# RF_PATH.net
KiCad netlist of a schematic drawn in Altium Designer
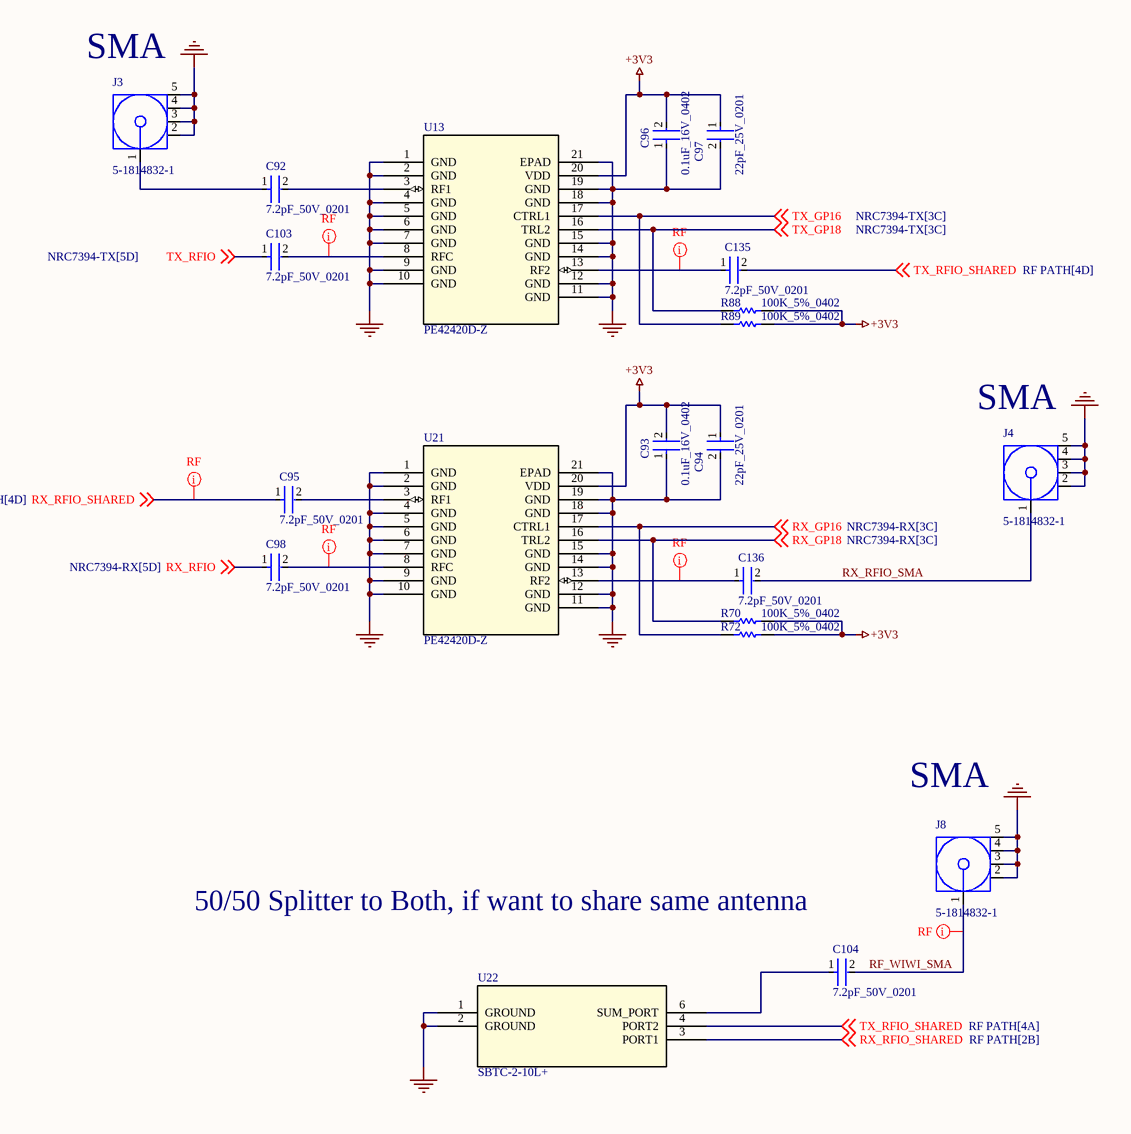
[diagram p0: RF PATH.SchDoc]

(export (version "E")
  (design (tool "Eeschema 10.0.6"))
  (components
    (comp (ref "C92")
      (value "7.2pF_50V_0201")
      (footprint "FP-GRM033-0_03-IPC_B")
      (description "Chip Multilayer Ceramic Capacitors for General Purpose, 0201, 7.2pF, C0G, 30ppm/°C, 0.1pF, 50V")
      (libsource (lib "Altium Content Vault") (part "b4654b650e69147ec39a6b967a45e02"))
    )
    (comp (ref "C93")
      (value "0.1uF_16V_0402")
      (footprint "FP-C0402-BB-MFG")
      (description "CAP CER 0.1UF 16V 20% X7R 0402")
      (fields
        (field (name "MANUFACTURER") "Kemet")
        (field (name "OCTOPART") "https://octopart.com/c0402c104m4ractu-kemet-10476575")
      )
      (libsource (lib "Altium Content Vault") (part "b4654b650e69147ec39a6b967a45e02"))
    )
    (comp (ref "C94")
      (value "22pF_25V_0201")
      (footprint "FP-0201-L_0_6_0_09-W_0_3-MFG")
      (description "General Purpose Ceramic Capacitor, 0201, 22pF, 5%, C0G, 30ppm/°C, 25V")
      (fields (field (name "VOLTAGE") "25V") (field (name "TOLERANCE") "5%"))
      (libsource (lib "Altium Content Vault") (part "b4654b650e69147ec39a6b967a45e02"))
    )
    (comp (ref "C95")
      (value "7.2pF_50V_0201")
      (footprint "FP-GRM033-0_03-IPC_B")
      (description "Chip Multilayer Ceramic Capacitors for General Purpose, 0201, 7.2pF, C0G, 30ppm/°C, 0.1pF, 50V")
      (libsource (lib "Altium Content Vault") (part "b4654b650e69147ec39a6b967a45e02"))
    )
    (comp (ref "C96")
      (value "0.1uF_16V_0402")
      (footprint "FP-C0402-BB-MFG")
      (description "CAP CER 0.1UF 16V 20% X7R 0402")
      (fields
        (field (name "MANUFACTURER") "Kemet")
        (field (name "OCTOPART") "https://octopart.com/c0402c104m4ractu-kemet-10476575")
      )
      (libsource (lib "Altium Content Vault") (part "b4654b650e69147ec39a6b967a45e02"))
    )
    (comp (ref "C97")
      (value "22pF_25V_0201")
      (footprint "FP-0201-L_0_6_0_09-W_0_3-MFG")
      (description "General Purpose Ceramic Capacitor, 0201, 22pF, 5%, C0G, 30ppm/°C, 25V")
      (fields (field (name "VOLTAGE") "25V") (field (name "TOLERANCE") "5%"))
      (libsource (lib "Altium Content Vault") (part "b4654b650e69147ec39a6b967a45e02"))
    )
    (comp (ref "C98")
      (value "7.2pF_50V_0201")
      (footprint "FP-GRM033-0_03-IPC_B")
      (description "Chip Multilayer Ceramic Capacitors for General Purpose, 0201, 7.2pF, C0G, 30ppm/°C, 0.1pF, 50V")
      (libsource (lib "Altium Content Vault") (part "b4654b650e69147ec39a6b967a45e02"))
    )
    (comp (ref "C103")
      (value "7.2pF_50V_0201")
      (footprint "FP-GRM033-0_03-IPC_B")
      (description "Chip Multilayer Ceramic Capacitors for General Purpose, 0201, 7.2pF, C0G, 30ppm/°C, 0.1pF, 50V")
      (libsource (lib "Altium Content Vault") (part "b4654b650e69147ec39a6b967a45e02"))
    )
    (comp (ref "C104")
      (value "7.2pF_50V_0201")
      (footprint "FP-GRM033-0_03-IPC_B")
      (description "Chip Multilayer Ceramic Capacitors for General Purpose, 0201, 7.2pF, C0G, 30ppm/°C, 0.1pF, 50V")
      (libsource (lib "Altium Content Vault") (part "b4654b650e69147ec39a6b967a45e02"))
    )
    (comp (ref "C135")
      (value "7.2pF_50V_0201")
      (footprint "FP-GRM033-0_03-IPC_B")
      (description "Chip Multilayer Ceramic Capacitors for General Purpose, 0201, 7.2pF, C0G, 30ppm/°C, 0.1pF, 50V")
      (libsource (lib "Altium Content Vault") (part "b4654b650e69147ec39a6b967a45e02"))
    )
    (comp (ref "C136")
      (value "7.2pF_50V_0201")
      (footprint "FP-GRM033-0_03-IPC_B")
      (description "Chip Multilayer Ceramic Capacitors for General Purpose, 0201, 7.2pF, C0G, 30ppm/°C, 0.1pF, 50V")
      (libsource (lib "Altium Content Vault") (part "b4654b650e69147ec39a6b967a45e02"))
    )
    (comp (ref "J3")
      (value "5-1814832-1")
      (footprint "TECO-5-1814832-1_V")
      (fields (field (name "MANUFACTURER") "TE Connectivity"))
      (libsource (lib "Altium Content Vault") (part "CN-S-4F-RF5"))
    )
    (comp (ref "J4")
      (value "5-1814832-1")
      (footprint "TECO-5-1814832-1_V")
      (fields (field (name "MANUFACTURER") "TE Connectivity"))
      (libsource (lib "Altium Content Vault") (part "CN-S-4F-RF5"))
    )
    (comp (ref "J8")
      (value "5-1814832-1")
      (footprint "TECO-5-1814832-1_V")
      (fields (field (name "MANUFACTURER") "TE Connectivity"))
      (libsource (lib "Altium Content Vault") (part "CN-S-4F-RF5"))
    )
    (comp (ref "R70")
      (value "100K_5%_0402")
      (footprint "RESC1005X37X25ML05T10")
      (fields (field (name "PART NUMBER") "RE0402DR-07100KL") (field (name "MANUFACTURER") "Yageo / Phycomp"))
      (libsource (lib "Altium Content Vault") (part "RES"))
    )
    (comp (ref "R72")
      (value "100K_5%_0402")
      (footprint "RESC1005X37X25ML05T10")
      (fields (field (name "PART NUMBER") "RE0402DR-07100KL") (field (name "MANUFACTURER") "Yageo / Phycomp"))
      (libsource (lib "Altium Content Vault") (part "RES"))
    )
    (comp (ref "R88")
      (value "100K_5%_0402")
      (footprint "RESC1005X37X25ML05T10")
      (fields (field (name "PART NUMBER") "RE0402DR-07100KL") (field (name "MANUFACTURER") "Yageo / Phycomp"))
      (libsource (lib "Altium Content Vault") (part "RES"))
    )
    (comp (ref "R89")
      (value "100K_5%_0402")
      (footprint "RESC1005X37X25ML05T10")
      (fields (field (name "PART NUMBER") "RE0402DR-07100KL") (field (name "MANUFACTURER") "Yageo / Phycomp"))
      (libsource (lib "Altium Content Vault") (part "RES"))
    )
    (comp (ref "U13")
      (value "PE42420D-Z")
      (footprint "LGA20_4X4_PSM")
      (description "No Description Available")
      (libsource (lib "PE42420D-Z") (part "PE42420D-Z"))
    )
    (comp (ref "U21")
      (value "PE42420D-Z")
      (footprint "LGA20_4X4_PSM")
      (description "No Description Available")
      (libsource (lib "PE42420D-Z") (part "PE42420D-Z"))
    )
    (comp (ref "U22")
      (value "SBTC-2-10L+")
      (footprint "AT1029_MNC")
      (description "No Description Available")
      (fields (field (name "COPYRIGHT") "Copyright (C) 2023 Ultra Librarian. All rights reserved."))
      (libsource (lib "SBTC-2-10L&plus_") (part "SBTC-2-10L+"))
    )
  )
  (nets
    (net (code "1") (name "+3V3") (class "Default")
      (node (ref "C93") (pin "2") (pinfunction "2_2") (pintype "passive"))
      (node (ref "C94") (pin "1") (pinfunction "1_1") (pintype "passive"))
      (node (ref "C96") (pin "2") (pinfunction "2_2") (pintype "passive"))
      (node (ref "C97") (pin "1") (pinfunction "1_1") (pintype "passive"))
      (node (ref "R70") (pin "1") (pinfunction "1_1") (pintype "passive"))
      (node (ref "R72") (pin "1") (pinfunction "1_1") (pintype "passive"))
      (node (ref "R88") (pin "1") (pinfunction "1_1") (pintype "passive"))
      (node (ref "R89") (pin "1") (pinfunction "1_1") (pintype "passive"))
      (node (ref "U13") (pin "20") (pinfunction "VDD_20") (pintype "power_in"))
      (node (ref "U21") (pin "20") (pinfunction "VDD_20") (pintype "power_in"))
    )
    (net (code "2") (name "/RF_WIWI_SMA") (class "Default")
      (node (ref "C104") (pin "2") (pinfunction "2_2") (pintype "passive"))
      (node (ref "J8") (pin "1") (pinfunction "1_1") (pintype "passive"))
    )
    (net (code "3") (name "/RX_RFIO_SMA") (class "Default")
      (node (ref "C136") (pin "2") (pinfunction "2_2") (pintype "passive"))
      (node (ref "J4") (pin "1") (pinfunction "1_1") (pintype "passive"))
    )
    (net (code "4") (name "GND") (class "Default")
      (node (ref "C93") (pin "1") (pinfunction "1_1") (pintype "passive"))
      (node (ref "C94") (pin "2") (pinfunction "2_2") (pintype "passive"))
      (node (ref "C96") (pin "1") (pinfunction "1_1") (pintype "passive"))
      (node (ref "C97") (pin "2") (pinfunction "2_2") (pintype "passive"))
      (node (ref "J3") (pin "2") (pinfunction "2_2") (pintype "passive"))
      (node (ref "J3") (pin "3") (pinfunction "3_3") (pintype "passive"))
      (node (ref "J3") (pin "4") (pinfunction "4_4") (pintype "passive"))
      (node (ref "J3") (pin "5") (pinfunction "5_5") (pintype "passive"))
      (node (ref "J4") (pin "2") (pinfunction "2_2") (pintype "passive"))
      (node (ref "J4") (pin "3") (pinfunction "3_3") (pintype "passive"))
      (node (ref "J4") (pin "4") (pinfunction "4_4") (pintype "passive"))
      (node (ref "J4") (pin "5") (pinfunction "5_5") (pintype "passive"))
      (node (ref "J8") (pin "2") (pinfunction "2_2") (pintype "passive"))
      (node (ref "J8") (pin "3") (pinfunction "3_3") (pintype "passive"))
      (node (ref "J8") (pin "4") (pinfunction "4_4") (pintype "passive"))
      (node (ref "J8") (pin "5") (pinfunction "5_5") (pintype "passive"))
      (node (ref "U13") (pin "1") (pinfunction "GND_1") (pintype "power_in"))
      (node (ref "U13") (pin "10") (pinfunction "GND_10") (pintype "power_in"))
      (node (ref "U13") (pin "11") (pinfunction "GND_11") (pintype "power_in"))
      (node (ref "U13") (pin "12") (pinfunction "GND_12") (pintype "power_in"))
      (node (ref "U13") (pin "14") (pinfunction "GND_14") (pintype "power_in"))
      (node (ref "U13") (pin "15") (pinfunction "GND_15") (pintype "power_in"))
      (node (ref "U13") (pin "18") (pinfunction "GND_18") (pintype "power_in"))
      (node (ref "U13") (pin "19") (pinfunction "GND_19") (pintype "power_in"))
      (node (ref "U13") (pin "2") (pinfunction "GND_2") (pintype "power_in"))
      (node (ref "U13") (pin "21") (pinfunction "EPAD_21") (pintype "passive"))
      (node (ref "U13") (pin "4") (pinfunction "GND_4") (pintype "power_in"))
      (node (ref "U13") (pin "5") (pinfunction "GND_5") (pintype "power_in"))
      (node (ref "U13") (pin "6") (pinfunction "GND_6") (pintype "power_in"))
      (node (ref "U13") (pin "7") (pinfunction "GND_7") (pintype "power_in"))
      (node (ref "U13") (pin "9") (pinfunction "GND_9") (pintype "power_in"))
      (node (ref "U21") (pin "1") (pinfunction "GND_1") (pintype "power_in"))
      (node (ref "U21") (pin "10") (pinfunction "GND_10") (pintype "power_in"))
      (node (ref "U21") (pin "11") (pinfunction "GND_11") (pintype "power_in"))
      (node (ref "U21") (pin "12") (pinfunction "GND_12") (pintype "power_in"))
      (node (ref "U21") (pin "14") (pinfunction "GND_14") (pintype "power_in"))
      (node (ref "U21") (pin "15") (pinfunction "GND_15") (pintype "power_in"))
      (node (ref "U21") (pin "18") (pinfunction "GND_18") (pintype "power_in"))
      (node (ref "U21") (pin "19") (pinfunction "GND_19") (pintype "power_in"))
      (node (ref "U21") (pin "2") (pinfunction "GND_2") (pintype "power_in"))
      (node (ref "U21") (pin "21") (pinfunction "EPAD_21") (pintype "passive"))
      (node (ref "U21") (pin "4") (pinfunction "GND_4") (pintype "power_in"))
      (node (ref "U21") (pin "5") (pinfunction "GND_5") (pintype "power_in"))
      (node (ref "U21") (pin "6") (pinfunction "GND_6") (pintype "power_in"))
      (node (ref "U21") (pin "7") (pinfunction "GND_7") (pintype "power_in"))
      (node (ref "U21") (pin "9") (pinfunction "GND_9") (pintype "power_in"))
      (node (ref "U22") (pin "1") (pinfunction "GROUND_1") (pintype "passive"))
      (node (ref "U22") (pin "2") (pinfunction "GROUND_2") (pintype "passive"))
    )
    (net (code "5") (name "Net-(C92-Pad1)") (class "Default")
      (node (ref "C92") (pin "1") (pinfunction "1_1") (pintype "passive"))
      (node (ref "J3") (pin "1") (pinfunction "1_1") (pintype "passive"))
    )
    (net (code "6") (name "Net-(U13-RF1)") (class "Default")
      (node (ref "C92") (pin "2") (pinfunction "2_2") (pintype "passive"))
      (node (ref "U13") (pin "3") (pinfunction "RF1_3") (pintype "bidirectional"))
    )
    (net (code "7") (name "Net-(U13-RF2)") (class "Default")
      (node (ref "C135") (pin "1") (pinfunction "1_1") (pintype "passive"))
      (node (ref "U13") (pin "13") (pinfunction "RF2_13") (pintype "bidirectional"))
    )
    (net (code "8") (name "Net-(U13-RFC)") (class "Default")
      (node (ref "C103") (pin "2") (pinfunction "2_2") (pintype "passive"))
      (node (ref "U13") (pin "8") (pinfunction "RFC_8") (pintype "passive"))
    )
    (net (code "9") (name "Net-(U21-RF1)") (class "Default")
      (node (ref "C95") (pin "2") (pinfunction "2_2") (pintype "passive"))
      (node (ref "U21") (pin "3") (pinfunction "RF1_3") (pintype "bidirectional"))
    )
    (net (code "10") (name "Net-(U21-RF2)") (class "Default")
      (node (ref "C136") (pin "1") (pinfunction "1_1") (pintype "passive"))
      (node (ref "U21") (pin "13") (pinfunction "RF2_13") (pintype "bidirectional"))
    )
    (net (code "11") (name "Net-(U21-RFC)") (class "Default")
      (node (ref "C98") (pin "2") (pinfunction "2_2") (pintype "passive"))
      (node (ref "U21") (pin "8") (pinfunction "RFC_8") (pintype "passive"))
    )
    (net (code "12") (name "Net-(U22-SUM_PORT)") (class "Default")
      (node (ref "C104") (pin "1") (pinfunction "1_1") (pintype "passive"))
      (node (ref "U22") (pin "6") (pinfunction "SUM_PORT_6") (pintype "passive"))
    )
    (net (code "13") (name "RX_GP16") (class "Default")
      (node (ref "R72") (pin "2") (pinfunction "2_2") (pintype "passive"))
      (node (ref "U21") (pin "17") (pinfunction "CTRL1_17") (pintype "passive"))
    )
    (net (code "14") (name "RX_GP18") (class "Default")
      (node (ref "R70") (pin "2") (pinfunction "2_2") (pintype "passive"))
      (node (ref "U21") (pin "16") (pinfunction "TRL2_16") (pintype "passive"))
    )
    (net (code "15") (name "RX_RFIO") (class "Default")
      (node (ref "C98") (pin "1") (pinfunction "1_1") (pintype "passive"))
    )
    (net (code "16") (name "RX_RFIO_SHARED") (class "Default")
      (node (ref "C95") (pin "1") (pinfunction "1_1") (pintype "passive"))
      (node (ref "U22") (pin "3") (pinfunction "PORT1_3") (pintype "passive"))
    )
    (net (code "17") (name "TX_GP16") (class "Default")
      (node (ref "R89") (pin "2") (pinfunction "2_2") (pintype "passive"))
      (node (ref "U13") (pin "17") (pinfunction "CTRL1_17") (pintype "passive"))
    )
    (net (code "18") (name "TX_GP18") (class "Default")
      (node (ref "R88") (pin "2") (pinfunction "2_2") (pintype "passive"))
      (node (ref "U13") (pin "16") (pinfunction "TRL2_16") (pintype "passive"))
    )
    (net (code "19") (name "TX_RFIO") (class "Default")
      (node (ref "C103") (pin "1") (pinfunction "1_1") (pintype "passive"))
    )
    (net (code "20") (name "TX_RFIO_SHARED") (class "Default")
      (node (ref "C135") (pin "2") (pinfunction "2_2") (pintype "passive"))
      (node (ref "U22") (pin "4") (pinfunction "PORT2_4") (pintype "passive"))
    )
  )
)
